# sheet3.net
KiCad netlist of a schematic drawn in Altium Designer
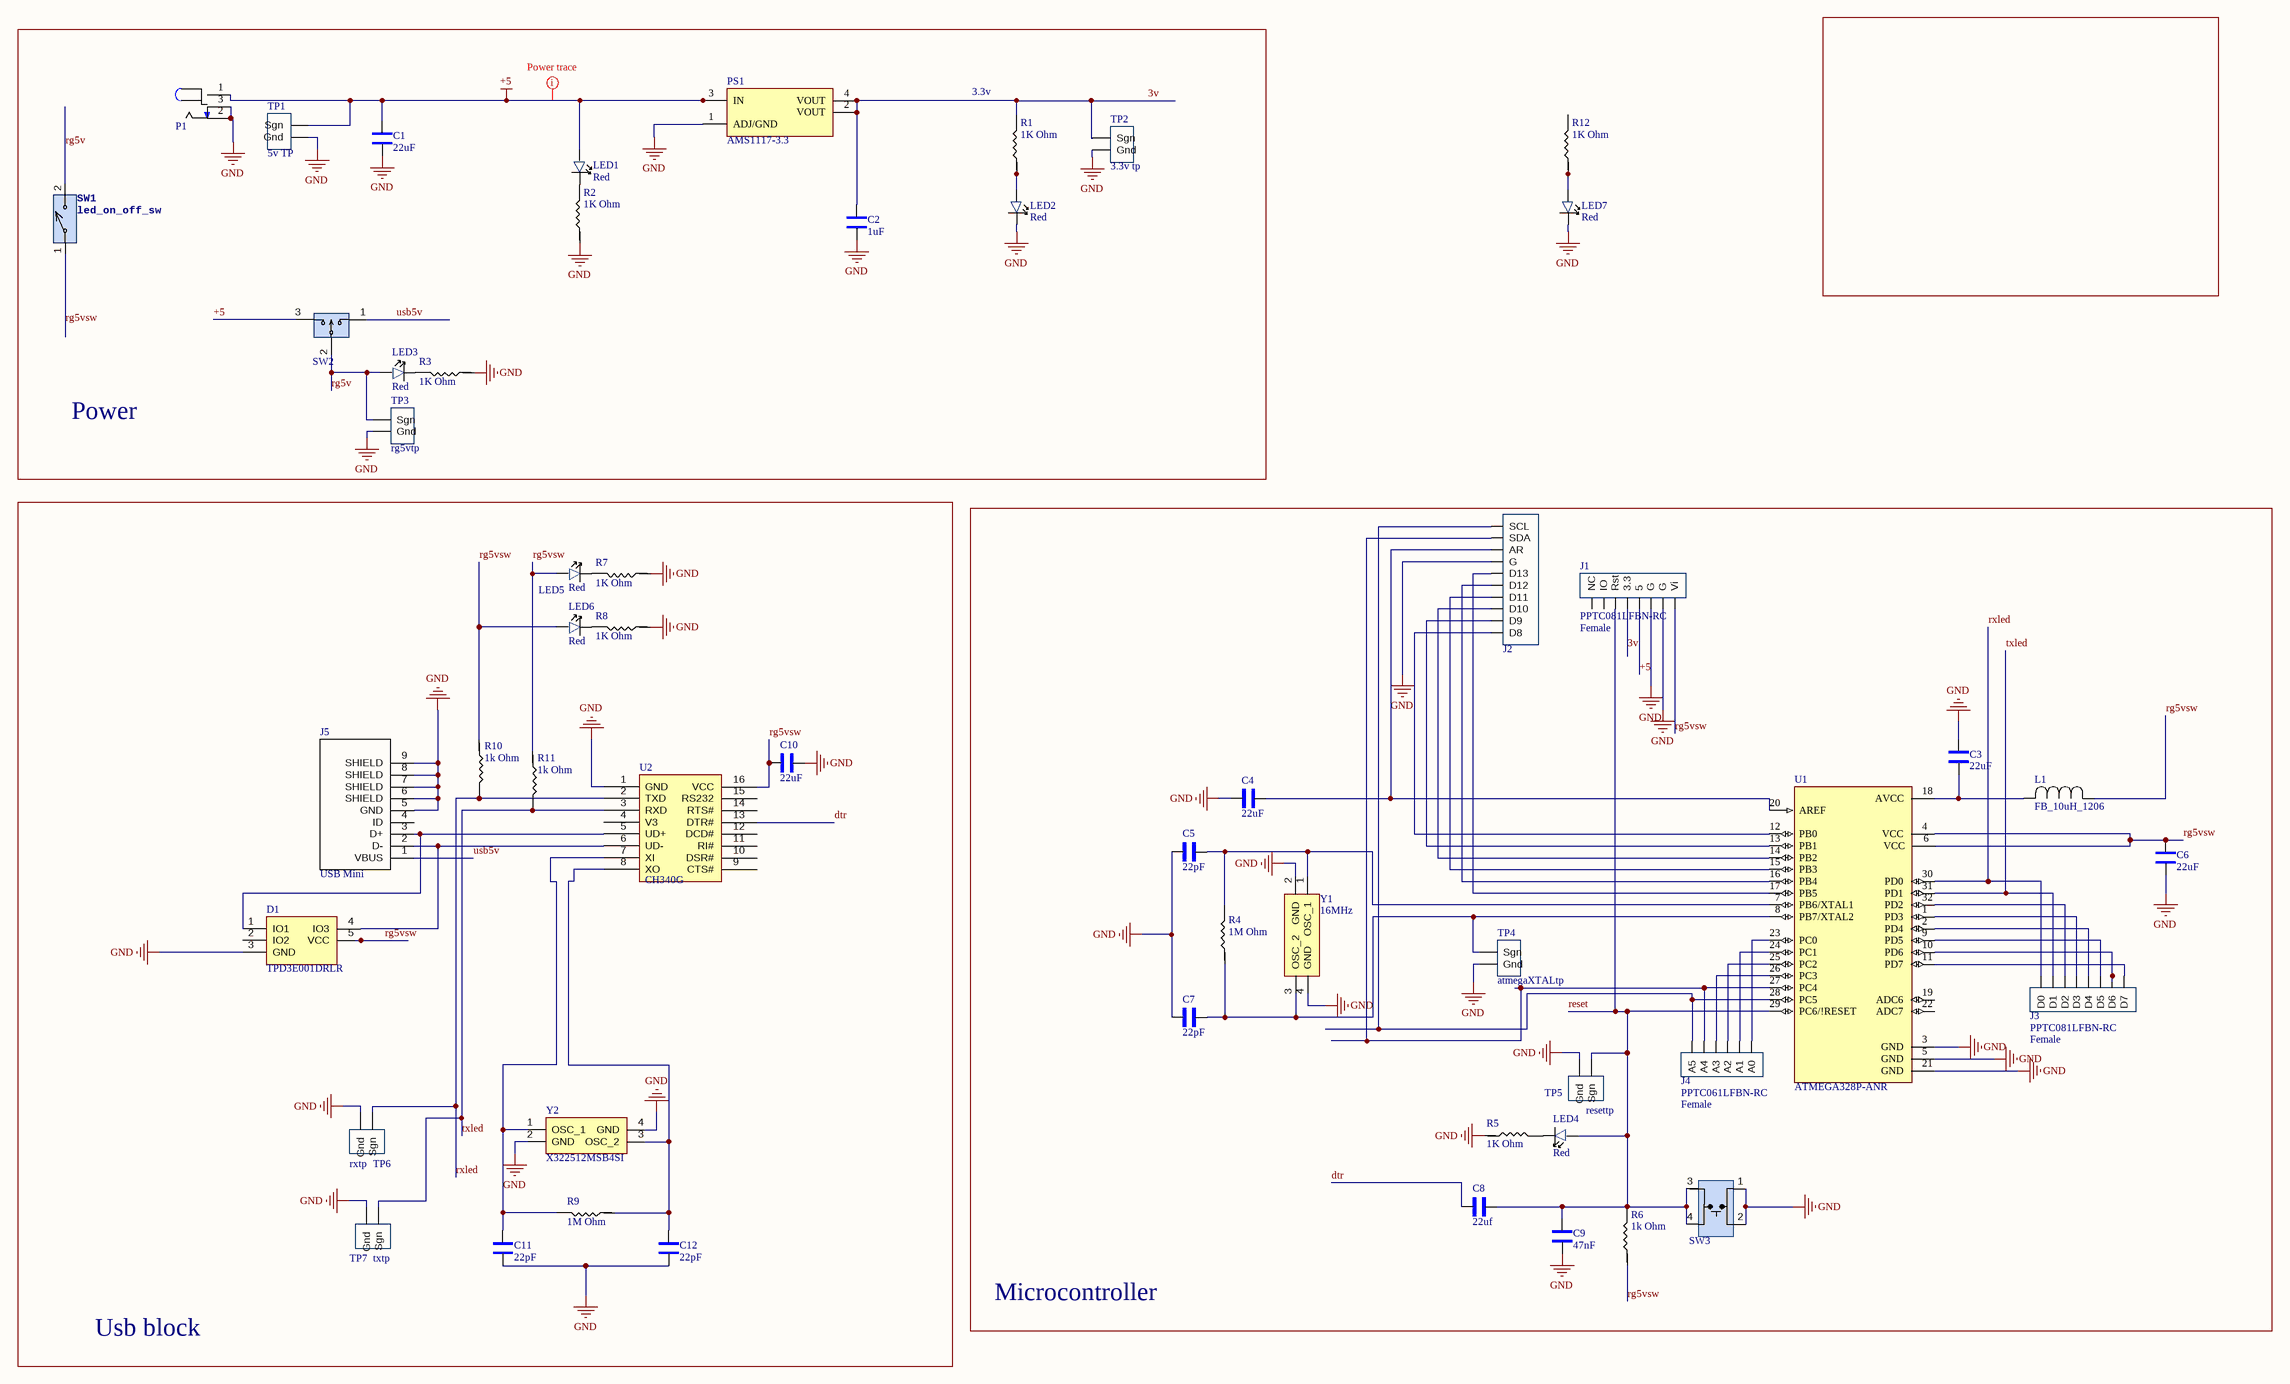
[diagram p0: sheet3.SchDoc]

(export (version "E")
  (design (tool "Eeschema 10.0.6"))
  (components
    (comp (ref "C1")
      (value "22uF")
      (footprint "1206_Passive_Capacitor")
      (description "22uF ±10% 25V X5R 1206 Multilayer Ceramic Capacitors MLCC - SMD/SMT RoHS")
      (fields (field (name "MFR PART #") "CL31A226KAHNNNE") (field (name "LCSC PART#") "C12891"))
      (libsource (lib "ECEN5730Lib_2023_05_DS") (part "C_22uF_1206"))
    )
    (comp (ref "C2")
      (value "1uF")
      (footprint "1206_Passive_Capacitor")
      (description "MULTILAYER CERAMIC CAPACITORS MLCC - SMD/SMT 1UF 50V 1206 ROHS")
      (fields (field (name "MFR PART #") "CL31B105KBHNNNE") (field (name "LCSC PART#") "C1848"))
      (libsource (lib "ECEN5730Lib_2023_05_DS") (part "C_1uF_1206"))
    )
    (comp (ref "C3")
      (value "22uF")
      (footprint "1206_Passive_Capacitor")
      (description "22uF ±10% 25V X5R 1206 Multilayer Ceramic Capacitors MLCC - SMD/SMT RoHS")
      (fields (field (name "MFR PART #") "CL31A226KAHNNNE") (field (name "LCSC PART#") "C12891"))
      (libsource (lib "ECEN5730Lib_2023_05_DS") (part "C_22uF_1206"))
    )
    (comp (ref "C4")
      (value "22uF")
      (footprint "1206_Passive_Capacitor")
      (description "22uF ±10% 25V X5R 1206 Multilayer Ceramic Capacitors MLCC - SMD/SMT RoHS")
      (fields (field (name "MFR PART #") "CL31A226KAHNNNE") (field (name "LCSC PART#") "C12891"))
      (libsource (lib "ECEN5730Lib_2023_05_DS") (part "C_22uF_1206"))
    )
    (comp (ref "C5")
      (value "22pF")
      (footprint "1206_Passive_Capacitor")
      (description "22pF ±5% 1kV C0G 1206 Multilayer Ceramic Capacitors MLCC - SMD/SMT RoHS")
      (fields (field (name "LCSC PART#") "C107174") (field (name "MFR PART #") "CC1206JKNPOCBN220"))
      (libsource (lib "ECEN5730Lib_2023_05_DS") (part "C_22pF_1206"))
    )
    (comp (ref "C6")
      (value "22uF")
      (footprint "1206_Passive_Capacitor")
      (description "22uF ±10% 25V X5R 1206 Multilayer Ceramic Capacitors MLCC - SMD/SMT RoHS")
      (fields (field (name "MFR PART #") "CL31A226KAHNNNE") (field (name "LCSC PART#") "C12891"))
      (libsource (lib "ECEN5730Lib_2023_05_DS") (part "C_22uF_1206"))
    )
    (comp (ref "C7")
      (value "22pF")
      (footprint "1206_Passive_Capacitor")
      (description "22pF ±5% 1kV C0G 1206 Multilayer Ceramic Capacitors MLCC - SMD/SMT RoHS")
      (fields (field (name "LCSC PART#") "C107174") (field (name "MFR PART #") "CC1206JKNPOCBN220"))
      (libsource (lib "ECEN5730Lib_2023_05_DS") (part "C_22pF_1206"))
    )
    (comp (ref "C8")
      (value "22uf")
      (footprint "1206_Passive_Capacitor")
      (description "MULTILAYER CERAMIC CAPACITORS MLCC - SMD/SMT 1UF 50V 1206 ROHS")
      (fields (field (name "MFR PART #") "CL31B105KBHNNNE") (field (name "LCSC PART#") "C1848"))
      (libsource (lib "ECEN5730Lib_2023_05_DS") (part "C_1uF_1206"))
    )
    (comp (ref "C9")
      (value "47nF")
      (footprint "1206_Passive_Capacitor")
      (description "47nF ±5% 50V C0G 1206 Multilayer Ceramic Capacitors MLCC - SMD/SMT RoHS")
      (fields (field (name "LCSC PART#") "C21812") (field (name "MFR PART #") "GRM31M5C1H473JA01L"))
      (libsource (lib "ECEN5730Lib_2023_05_DS") (part "C_47nF_1206"))
    )
    (comp (ref "C10")
      (value "22uF")
      (footprint "1206_Passive_Capacitor")
      (description "22uF ±10% 25V X5R 1206 Multilayer Ceramic Capacitors MLCC - SMD/SMT RoHS")
      (fields (field (name "MFR PART #") "CL31A226KAHNNNE") (field (name "LCSC PART#") "C12891"))
      (libsource (lib "ECEN5730Lib_2023_05_DS") (part "C_22uF_1206"))
    )
    (comp (ref "C11")
      (value "22pF")
      (footprint "1206_Passive_Capacitor")
      (description "22pF ±5% 1kV C0G 1206 Multilayer Ceramic Capacitors MLCC - SMD/SMT RoHS")
      (fields (field (name "LCSC PART#") "C107174") (field (name "MFR PART #") "CC1206JKNPOCBN220"))
      (libsource (lib "ECEN5730Lib_2023_05_DS") (part "C_22pF_1206"))
    )
    (comp (ref "C12")
      (value "22pF")
      (footprint "1206_Passive_Capacitor")
      (description "22pF ±5% 1kV C0G 1206 Multilayer Ceramic Capacitors MLCC - SMD/SMT RoHS")
      (fields (field (name "LCSC PART#") "C107174") (field (name "MFR PART #") "CC1206JKNPOCBN220"))
      (libsource (lib "ECEN5730Lib_2023_05_DS") (part "C_22pF_1206"))
    )
    (comp (ref "D1")
      (value "TPD3E001DRLR")
      (footprint "SOTFL50P160X60-5N")
      (description "Low-Capacitance 3-Channel +/-15KV ESD-Protection Array for High-Speed Data Interfaces")
      (fields (field (name "MOUSER PART NUMBER") "595-TPD3E001DRLR"))
      (libsource (lib "TPD3E001DRLR") (part "TPD3E001DRLR"))
    )
    (comp (ref "J1")
      (value "PPTC081LFBN-RC")
      (footprint "8_PIN_ARD-PWR_100MIL")
      (description "8 Position Header Connector 0.100\" (2.54mm) Through Hole Tin")
      (fields (field (name "LCSC PART#") "C27438") (field (name "ALTIUM_VALUE") "Female"))
      (libsource (lib "ECEN5730Lib_2023_05_DS") (part "JF_8_PIN_FEMA_ARD-Pwr"))
    )
    (comp (ref "J2")
      (value "PPTC101LFBN-RC")
      (footprint "10_PIN_ARDUINO_100MIL")
      (description "10 Position Header Connector 0.100\" (2.54mm) Through Hole Tin")
      (fields (field (name "LCSC PART#") "C225507"))
      (libsource (lib "ECEN5730Lib_2023_05_DS") (part "JF_10_PIN_FEMA_ARDUINO"))
    )
    (comp (ref "J3")
      (value "PPTC081LFBN-RC")
      (footprint "8_PIN_ARD-DIG_100MIL")
      (description "8 Position Header Connector 0.100\" (2.54mm) Through Hole Tin")
      (fields (field (name "LCSC PART#") "C27438") (field (name "ALTIUM_VALUE") "Female"))
      (libsource (lib "ECEN5730Lib_2023_05_DS") (part "JF_8_PIN_FEMA_ARD-Dig"))
    )
    (comp (ref "J4")
      (value "PPTC061LFBN-RC")
      (footprint "6_PIN_ARD-Analog_100mil")
      (description "6 Position Header Connector 0.100\" (2.54mm) Through Hole Tin")
      (fields (field (name "LCSC PART#") "C40877") (field (name "ALTIUM_VALUE") "Female"))
      (libsource (lib "ECEN5730Lib_2023_05_DS") (part "JF_6_PIN_FEMA_ARD-Anolog"))
    )
    (comp (ref "J5")
      (value "USB Mini")
      (footprint "USB_MINI_B")
      (description "Through Hole USB Connectors RoHS")
      (fields (field (name "LCSC PART#") "C46398") (field (name "MFR PART #") "920-462A2021D10102"))
      (libsource (lib "ECEN5730Lib_2023_05_DS") (part "J_USB_B_Mini"))
    )
    (comp (ref "L1")
      (value "FB_10uH_1206")
      (footprint "AIML-1206_ABR-M")
      (description "25mA 10uH ±10% 800mΩ 1206  Inductors (SMD) ROHS")
      (fields (field (name "MFR PART #") "CMI321609X100KT") (field (name "LCSC PART#") "C1051"))
      (libsource (lib "ECEN5730Lib_2023_05_DS") (part "FB_10uH_1206"))
    )
    (comp (ref "LED1")
      (value "Red")
      (footprint "LED_1206")
      (description "Red 621~631nm 1206 Light Emitting Diodes (LED) RoHS")
      (fields (field (name "MFR PART #") "15-21/R6C-FQ1R1B/2T") (field (name "LCSC PART#") "C93133"))
      (libsource (lib "ECEN5730Lib_2023_05_DS") (part "LED_RED_1206"))
    )
    (comp (ref "LED2")
      (value "Red")
      (footprint "LED_1206")
      (description "Red 621~631nm 1206 Light Emitting Diodes (LED) RoHS")
      (fields (field (name "MFR PART #") "15-21/R6C-FQ1R1B/2T") (field (name "LCSC PART#") "C93133"))
      (libsource (lib "ECEN5730Lib_2023_05_DS") (part "LED_RED_1206"))
    )
    (comp (ref "LED3")
      (value "Red")
      (footprint "LED_1206")
      (description "Red 621~631nm 1206 Light Emitting Diodes (LED) RoHS")
      (fields (field (name "MFR PART #") "15-21/R6C-FQ1R1B/2T") (field (name "LCSC PART#") "C93133"))
      (libsource (lib "ECEN5730Lib_2023_05_DS") (part "LED_RED_1206"))
    )
    (comp (ref "LED4")
      (value "Red")
      (footprint "LED_1206")
      (description "Red 621~631nm 1206 Light Emitting Diodes (LED) RoHS")
      (fields (field (name "MFR PART #") "15-21/R6C-FQ1R1B/2T") (field (name "LCSC PART#") "C93133"))
      (libsource (lib "ECEN5730Lib_2023_05_DS") (part "LED_RED_1206"))
    )
    (comp (ref "LED5")
      (value "Red")
      (footprint "LED_1206")
      (description "Red 621~631nm 1206 Light Emitting Diodes (LED) RoHS")
      (fields (field (name "MFR PART #") "15-21/R6C-FQ1R1B/2T") (field (name "LCSC PART#") "C93133"))
      (libsource (lib "ECEN5730Lib_2023_05_DS") (part "LED_RED_1206"))
    )
    (comp (ref "LED6")
      (value "Red")
      (footprint "LED_1206")
      (description "Red 621~631nm 1206 Light Emitting Diodes (LED) RoHS")
      (fields (field (name "MFR PART #") "15-21/R6C-FQ1R1B/2T") (field (name "LCSC PART#") "C93133"))
      (libsource (lib "ECEN5730Lib_2023_05_DS") (part "LED_RED_1206"))
    )
    (comp (ref "LED7")
      (value "Red")
      (footprint "LED_1206")
      (description "Red 621~631nm 1206 Light Emitting Diodes (LED) RoHS")
      (fields (field (name "MFR PART #") "15-21/R6C-FQ1R1B/2T") (field (name "LCSC PART#") "C93133"))
      (libsource (lib "ECEN5730Lib_2023_05_DS") (part "LED_RED_1206"))
    )
    (comp (ref "P1")
      (value "Power Jack")
      (footprint "Power_Jack")
      (description "Power Barrel Connector Jack 2.10mm ID (0.083\"), 5.50mm OD (0.217\") Through Hole, Right Angle")
      (fields (field (name "MFR PART #") "PJ-102A") (field (name "LCSC PART#") "C136744"))
      (libsource (lib "ECEN5730Lib_2023_05_DS") (part "P_Power Jack"))
    )
    (comp (ref "PS1")
      (value "AMS1117-3.3")
      (footprint "LDO")
      (description "LOW DROPOUT REGULATORS(LDO) POSITIVE FIXED 1.3V @ 800MA 15V 3.3V 1A SOT-223 ROHS")
      (fields (field (name "LCSC PART#") "C6186"))
      (libsource (lib "ECEN5730Lib_2023_05_DS") (part "PS_AMS_LDO_3v3"))
    )
    (comp (ref "R1")
      (value "1K Ohm")
      (footprint "1206_Passive_Resitor")
      (description "CHIP RESISTOR - SURFACE MOUNT 1KOHMS ±1% 1/4W 1206 ROHS")
      (fields (field (name "MFR PART #") "RNCP1206FTD1K00CT") (field (name "LCSC PART#") "C4410"))
      (libsource (lib "ECEN5730Lib_2023_05_DS") (part "R_1K_1206"))
    )
    (comp (ref "R2")
      (value "1K Ohm")
      (footprint "1206_Passive_Resitor")
      (description "CHIP RESISTOR - SURFACE MOUNT 1KOHMS ±1% 1/4W 1206 ROHS")
      (fields (field (name "MFR PART #") "RNCP1206FTD1K00CT") (field (name "LCSC PART#") "C4410"))
      (libsource (lib "ECEN5730Lib_2023_05_DS") (part "R_1K_1206"))
    )
    (comp (ref "R3")
      (value "1K Ohm")
      (footprint "1206_Passive_Resitor")
      (description "CHIP RESISTOR - SURFACE MOUNT 1KOHMS ±1% 1/4W 1206 ROHS")
      (fields (field (name "MFR PART #") "RNCP1206FTD1K00CT") (field (name "LCSC PART#") "C4410"))
      (libsource (lib "ECEN5730Lib_2023_05_DS") (part "R_1K_1206"))
    )
    (comp (ref "R4")
      (value "1M Ohm")
      (footprint "1206_Passive_Resitor")
      (description "CHIP RESISTOR - SURFACE MOUNT 1MOHMS ±1% 1/4W 1206 ROHS")
      (fields (field (name "MFR PART #") "RMCF1206JT1M00") (field (name "LCSC PART#") "C17927"))
      (libsource (lib "ECEN5730Lib_2023_05_DS") (part "R_1M_1206"))
    )
    (comp (ref "R5")
      (value "1K Ohm")
      (footprint "1206_Passive_Resitor")
      (description "CHIP RESISTOR - SURFACE MOUNT 1KOHMS ±1% 1/4W 1206 ROHS")
      (fields (field (name "MFR PART #") "RNCP1206FTD1K00CT") (field (name "LCSC PART#") "C4410"))
      (libsource (lib "ECEN5730Lib_2023_05_DS") (part "R_1K_1206"))
    )
    (comp (ref "R6")
      (value "1k Ohm")
      (footprint "1206_Passive_Resitor")
      (description "10 kOhms ±5% 0.25W, 1/4W Chip Resistor 1206 (3216 Metric) Automotive AEC-Q200 Thick Film")
      (fields (field (name "MFR PART #") "RMCF1206FT10K0") (field (name "LCSC PART#") "C17902"))
      (libsource (lib "ECEN5730Lib_2023_05_DS") (part "R_10KOhm_1206"))
    )
    (comp (ref "R7")
      (value "1K Ohm")
      (footprint "1206_Passive_Resitor")
      (description "CHIP RESISTOR - SURFACE MOUNT 1KOHMS ±1% 1/4W 1206 ROHS")
      (fields (field (name "MFR PART #") "RNCP1206FTD1K00CT") (field (name "LCSC PART#") "C4410"))
      (libsource (lib "ECEN5730Lib_2023_05_DS") (part "R_1K_1206"))
    )
    (comp (ref "R8")
      (value "1K Ohm")
      (footprint "1206_Passive_Resitor")
      (description "CHIP RESISTOR - SURFACE MOUNT 1KOHMS ±1% 1/4W 1206 ROHS")
      (fields (field (name "MFR PART #") "RNCP1206FTD1K00CT") (field (name "LCSC PART#") "C4410"))
      (libsource (lib "ECEN5730Lib_2023_05_DS") (part "R_1K_1206"))
    )
    (comp (ref "R9")
      (value "1M Ohm")
      (footprint "1206_Passive_Resitor")
      (description "CHIP RESISTOR - SURFACE MOUNT 1MOHMS ±1% 1/4W 1206 ROHS")
      (fields (field (name "MFR PART #") "RMCF1206JT1M00") (field (name "LCSC PART#") "C17927"))
      (libsource (lib "ECEN5730Lib_2023_05_DS") (part "R_1M_1206"))
    )
    (comp (ref "R10")
      (value "1k Ohm")
      (footprint "1206_Passive_Resitor")
      (description "CHIP RESISTOR - SURFACE MOUNT 1MOHMS ±1% 1/4W 1206 ROHS")
      (fields (field (name "MFR PART #") "RMCF1206JT1M00") (field (name "LCSC PART#") "C17927"))
      (libsource (lib "ECEN5730Lib_2023_05_DS") (part "R_1M_1206"))
    )
    (comp (ref "R11")
      (value "1k Ohm")
      (footprint "1206_Passive_Resitor")
      (description "CHIP RESISTOR - SURFACE MOUNT 1MOHMS ±1% 1/4W 1206 ROHS")
      (fields (field (name "MFR PART #") "RMCF1206JT1M00") (field (name "LCSC PART#") "C17927"))
      (libsource (lib "ECEN5730Lib_2023_05_DS") (part "R_1M_1206"))
    )
    (comp (ref "R12")
      (value "1K Ohm")
      (footprint "1206_Passive_Resitor")
      (description "CHIP RESISTOR - SURFACE MOUNT 1KOHMS ±1% 1/4W 1206 ROHS")
      (fields (field (name "MFR PART #") "RNCP1206FTD1K00CT") (field (name "LCSC PART#") "C4410"))
      (libsource (lib "ECEN5730Lib_2023_05_DS") (part "R_1K_1206"))
    )
    (comp (ref "SW1")
      (value "led_on_off_sw")
      (footprint "2Pin-Header-Conn")
      (description "2Pin Header")
      (fields (field (name "LCSC PART#") "C124375"))
      (libsource (lib "ECEN5730Lib_2023_05_DS") (part "SW_2Pin_100mil_Switch"))
    )
    (comp (ref "SW2")
      (value "PREC003SAAN-RC")
      (footprint "3_PIN_100mil")
      (description "Connector Header Through Hole 3 position 0.100\" (2.54mm)")
      (fields (field (name "LCSC PART#") "C49257"))
      (libsource (lib "ECEN5730Lib_2023_05_DS") (part "SW_3Pin_100mil_Switch"))
    )
    (comp (ref "SW3")
      (value "TL3305AF160QG")
      (footprint "Switch_JLC")
      (description "Tactile Switch SPST-NO Top Actuated Surface Mount")
      (fields (field (name "MFR PART #") "KH-4.5X4.5X4.3H-STM") (field (name "LCSC PART#") "C2837550"))
      (libsource (lib "ECEN5730Lib_2023_05_DS") (part "SW_Push_Button_JLC"))
    )
    (comp (ref "TP1")
      (value "5v TP")
      (footprint "TP10x_Probe")
      (description "Test Point 300 mil centers")
      (libsource (lib "ECEN5730Lib_2023_05_DS") (part "TP_10x_Probe"))
    )
    (comp (ref "TP2")
      (value "3.3v tp")
      (footprint "TP10x_Probe")
      (description "Test Point 300 mil centers")
      (libsource (lib "") (part "TP_10x_Probe_1"))
    )
    (comp (ref "TP3")
      (value "rg5vtp")
      (footprint "TP10x_Probe")
      (description "Test Point 300 mil centers")
      (libsource (lib "") (part "TP_10x_Probe_1"))
    )
    (comp (ref "TP4")
      (value "atmegaXTALtp")
      (footprint "TP10x_Probe")
      (description "Test Point 300 mil centers")
      (libsource (lib "") (part "TP_10x_Probe_1"))
    )
    (comp (ref "TP5")
      (value "resettp")
      (footprint "TP10x_Probe")
      (description "Test Point 300 mil centers")
      (libsource (lib "ECEN5730Lib_2023_05_DS") (part "TP_10x_Probe"))
    )
    (comp (ref "TP6")
      (value "rxtp")
      (footprint "TP10x_Probe")
      (description "Test Point 300 mil centers")
      (libsource (lib "ECEN5730Lib_2023_05_DS") (part "TP_10x_Probe"))
    )
    (comp (ref "TP7")
      (value "txtp")
      (footprint "TP10x_Probe")
      (description "Test Point 300 mil centers")
      (libsource (lib "ECEN5730Lib_2023_05_DS") (part "TP_10x_Probe"))
    )
    (comp (ref "U1")
      (value "ATMEGA328P-ANR")
      (footprint "ATMega328P")
      (description "AVR AVR® ATmega Microcontroller IC 8-Bit 20MHz 32KB (16K x 16) FLASH 32-TQFP (7x7)")
      (fields (field (name "MFR PART #") "ATMEGA328P-AU") (field (name "LCSC PART#") "C14877"))
      (libsource (lib "ECEN5730Lib_2023_05_DS") (part "U_ATMega328P"))
    )
    (comp (ref "U2")
      (value "CH340G")
      (footprint "USB to serial")
      (description "Transceiver USB 2.0 2Mbps SOP-16_150mil USB ICs RoHS")
      (fields (field (name "LCSC PART#") "C14267"))
      (libsource (lib "ECEN5730Lib_2023_05_DS") (part "U_USBtoSerial"))
    )
    (comp (ref "Y1")
      (value "16MHz")
      (footprint "Crystal resonator")
      (description "±10ppm 16000000Hz -40℃~85℃ 贴片无源晶振 60Ω 9pF SMD3225-4P Crystals ROHS")
      (fields (field (name "LCSC PART#") "C13738") (field (name "MFR PART #") "X322516MLB4SI"))
      (libsource (lib "ECEN5730Lib_2023_05_DS") (part "X_16Mhz_Res"))
    )
    (comp (ref "Y2")
      (value "X322512MSB4SI")
      (footprint "Crystal resonator")
      (description "SMD Crystal Resonators 12MHz ±10ppm SMD-3225_4P RoHS")
      (fields (field (name "LCSC PART#") "C9002"))
      (libsource (lib "ECEN5730Lib_2023_05_DS") (part "X_12MHz_Res"))
    )
  )
  (nets
    (net (code "1") (name "+5") (class "Default")
      (node (ref "C1") (pin "2") (pinfunction "2_2") (pintype "passive"))
      (node (ref "J1") (pin "5") (pinfunction "5_5") (pintype "passive"))
      (node (ref "LED1") (pin "1") (pinfunction "1_1") (pintype "passive"))
      (node (ref "P1") (pin "1") (pinfunction "1_1") (pintype "power_in"))
      (node (ref "PS1") (pin "3") (pinfunction "IN_3") (pintype "power_in"))
      (node (ref "SW2") (pin "3") (pinfunction "3_3") (pintype "passive"))
      (node (ref "TP1") (pin "1") (pinfunction "Sgn_1") (pintype "passive"))
    )
    (net (code "2") (name "/3v") (class "Default")
      (node (ref "C2") (pin "2") (pinfunction "2_2") (pintype "passive"))
      (node (ref "J1") (pin "4") (pinfunction "3.3_4") (pintype "passive"))
      (node (ref "PS1") (pin "2") (pinfunction "VOUT_2") (pintype "power_in"))
      (node (ref "PS1") (pin "4") (pinfunction "VOUT_4") (pintype "power_in"))
      (node (ref "R1") (pin "2") (pinfunction "2_2") (pintype "passive"))
      (node (ref "TP2") (pin "1") (pinfunction "Sgn_1") (pintype "passive"))
    )
    (net (code "3") (name "/dtr") (class "Default")
      (node (ref "C8") (pin "1") (pinfunction "1_1") (pintype "passive"))
      (node (ref "U2") (pin "13") (pinfunction "DTR#_13") (pintype "passive"))
    )
    (net (code "4") (name "/reset") (class "Default")
      (node (ref "C8") (pin "2") (pinfunction "2_2") (pintype "passive"))
      (node (ref "C9") (pin "2") (pinfunction "2_2") (pintype "passive"))
      (node (ref "J1") (pin "3") (pinfunction "Rst_3") (pintype "passive"))
      (node (ref "LED4") (pin "1") (pinfunction "1_1") (pintype "passive"))
      (node (ref "R6") (pin "2") (pinfunction "2_2") (pintype "passive"))
      (node (ref "SW3") (pin "3") (pinfunction "3_3") (pintype "passive"))
      (node (ref "SW3") (pin "4") (pinfunction "4_4") (pintype "passive"))
      (node (ref "TP5") (pin "1") (pinfunction "Sgn_1") (pintype "passive"))
      (node (ref "U1") (pin "29") (pinfunction "PC6/!RESET_29") (pintype "bidirectional"))
    )
    (net (code "5") (name "/rg5v") (class "Default")
      (node (ref "LED3") (pin "1") (pinfunction "1_1") (pintype "passive"))
      (node (ref "SW1") (pin "2") (pinfunction "2_2") (pintype "passive"))
      (node (ref "SW2") (pin "2") (pinfunction "2_2") (pintype "passive"))
      (node (ref "TP3") (pin "1") (pinfunction "Sgn_1") (pintype "passive"))
    )
    (net (code "6") (name "/rg5vsw") (class "Default")
      (node (ref "C10") (pin "1") (pinfunction "1_1") (pintype "passive"))
      (node (ref "C6") (pin "2") (pinfunction "2_2") (pintype "passive"))
      (node (ref "D1") (pin "5") (pinfunction "VCC_5") (pintype "passive"))
      (node (ref "J1") (pin "8") (pinfunction "Vi_8") (pintype "passive"))
      (node (ref "L1") (pin "1") (pinfunction "1_1") (pintype "passive"))
      (node (ref "LED5") (pin "1") (pinfunction "1_1") (pintype "passive"))
      (node (ref "LED6") (pin "1") (pinfunction "1_1") (pintype "passive"))
      (node (ref "R10") (pin "1") (pinfunction "1_1") (pintype "passive"))
      (node (ref "R11") (pin "1") (pinfunction "1_1") (pintype "passive"))
      (node (ref "R6") (pin "1") (pinfunction "1_1") (pintype "passive"))
      (node (ref "SW1") (pin "1") (pinfunction "1_1") (pintype "passive"))
      (node (ref "U1") (pin "4") (pinfunction "VCC_4") (pintype "power_in"))
      (node (ref "U1") (pin "6") (pinfunction "VCC_6") (pintype "power_in"))
      (node (ref "U2") (pin "16") (pinfunction "VCC_16") (pintype "passive"))
    )
    (net (code "7") (name "/rxled") (class "Default")
      (node (ref "J3") (pin "8") (pinfunction "D0_8") (pintype "passive"))
      (node (ref "R10") (pin "2") (pinfunction "2_2") (pintype "passive"))
      (node (ref "TP6") (pin "1") (pinfunction "Sgn_1") (pintype "passive"))
      (node (ref "U1") (pin "30") (pinfunction "PD0_30") (pintype "bidirectional"))
      (node (ref "U2") (pin "2") (pinfunction "TXD_2") (pintype "passive"))
    )
    (net (code "8") (name "/txled") (class "Default")
      (node (ref "J3") (pin "7") (pinfunction "D1_7") (pintype "passive"))
      (node (ref "R11") (pin "2") (pinfunction "2_2") (pintype "passive"))
      (node (ref "TP7") (pin "1") (pinfunction "Sgn_1") (pintype "passive"))
      (node (ref "U1") (pin "31") (pinfunction "PD1_31") (pintype "bidirectional"))
      (node (ref "U2") (pin "3") (pinfunction "RXD_3") (pintype "passive"))
    )
    (net (code "9") (name "/usb5v") (class "Default")
      (node (ref "J5") (pin "1") (pinfunction "VBUS_1") (pintype "passive"))
      (node (ref "SW2") (pin "1") (pinfunction "1_1") (pintype "passive"))
    )
    (net (code "10") (name "GND") (class "Default")
      (node (ref "C1") (pin "1") (pinfunction "1_1") (pintype "passive"))
      (node (ref "C10") (pin "2") (pinfunction "2_2") (pintype "passive"))
      (node (ref "C11") (pin "1") (pinfunction "1_1") (pintype "passive"))
      (node (ref "C12") (pin "1") (pinfunction "1_1") (pintype "passive"))
      (node (ref "C2") (pin "1") (pinfunction "1_1") (pintype "passive"))
      (node (ref "C3") (pin "2") (pinfunction "2_2") (pintype "passive"))
      (node (ref "C4") (pin "2") (pinfunction "2_2") (pintype "passive"))
      (node (ref "C5") (pin "1") (pinfunction "1_1") (pintype "passive"))
      (node (ref "C6") (pin "1") (pinfunction "1_1") (pintype "passive"))
      (node (ref "C7") (pin "1") (pinfunction "1_1") (pintype "passive"))
      (node (ref "C9") (pin "1") (pinfunction "1_1") (pintype "passive"))
      (node (ref "D1") (pin "3") (pinfunction "GND_3") (pintype "passive"))
      (node (ref "J1") (pin "6") (pinfunction "G_6") (pintype "passive"))
      (node (ref "J1") (pin "7") (pinfunction "G_7") (pintype "passive"))
      (node (ref "J2") (pin "4") (pinfunction "G_4") (pintype "passive"))
      (node (ref "J5") (pin "5") (pinfunction "GND_5") (pintype "passive"))
      (node (ref "J5") (pin "6") (pinfunction "SHIELD_6") (pintype "passive"))
      (node (ref "J5") (pin "7") (pinfunction "SHIELD_7") (pintype "passive"))
      (node (ref "J5") (pin "8") (pinfunction "SHIELD_8") (pintype "passive"))
      (node (ref "J5") (pin "9") (pinfunction "SHIELD_9") (pintype "passive"))
      (node (ref "LED2") (pin "2") (pinfunction "2_2") (pintype "passive"))
      (node (ref "LED7") (pin "2") (pinfunction "2_2") (pintype "passive"))
      (node (ref "P1") (pin "2") (pinfunction "2_2") (pintype "power_in"))
      (node (ref "P1") (pin "3") (pinfunction "3_3") (pintype "power_in"))
      (node (ref "PS1") (pin "1") (pinfunction "ADJ/GND_1") (pintype "passive"))
      (node (ref "R2") (pin "1") (pinfunction "1_1") (pintype "passive"))
      (node (ref "R3") (pin "1") (pinfunction "1_1") (pintype "passive"))
      (node (ref "R5") (pin "1") (pinfunction "1_1") (pintype "passive"))
      (node (ref "R7") (pin "1") (pinfunction "1_1") (pintype "passive"))
      (node (ref "R8") (pin "1") (pinfunction "1_1") (pintype "passive"))
      (node (ref "SW3") (pin "1") (pinfunction "1_1") (pintype "passive"))
      (node (ref "SW3") (pin "2") (pinfunction "2_2") (pintype "passive"))
      (node (ref "TP1") (pin "2") (pinfunction "Gnd_2") (pintype "passive"))
      (node (ref "TP2") (pin "2") (pinfunction "Gnd_2") (pintype "passive"))
      (node (ref "TP3") (pin "2") (pinfunction "Gnd_2") (pintype "passive"))
      (node (ref "TP4") (pin "2") (pinfunction "Gnd_2") (pintype "passive"))
      (node (ref "TP5") (pin "2") (pinfunction "Gnd_2") (pintype "passive"))
      (node (ref "TP6") (pin "2") (pinfunction "Gnd_2") (pintype "passive"))
      (node (ref "TP7") (pin "2") (pinfunction "Gnd_2") (pintype "passive"))
      (node (ref "U1") (pin "21") (pinfunction "GND_21") (pintype "power_in"))
      (node (ref "U1") (pin "3") (pinfunction "GND_3") (pintype "power_in"))
      (node (ref "U1") (pin "5") (pinfunction "GND_5") (pintype "power_in"))
      (node (ref "U2") (pin "1") (pinfunction "GND_1") (pintype "passive"))
      (node (ref "Y1") (pin "2") (pinfunction "GND_2") (pintype "passive"))
      (node (ref "Y1") (pin "4") (pinfunction "GND_4") (pintype "passive"))
      (node (ref "Y2") (pin "2") (pinfunction "GND_2") (pintype "passive"))
      (node (ref "Y2") (pin "4") (pinfunction "GND_4") (pintype "passive"))
    )
    (net (code "11") (name "Net-(D1-IO1)") (class "Default")
      (node (ref "D1") (pin "1") (pinfunction "IO1_1") (pintype "passive"))
      (node (ref "J5") (pin "3") (pinfunction "D+_3") (pintype "passive"))
      (node (ref "U2") (pin "5") (pinfunction "UD+_5") (pintype "passive"))
    )
    (net (code "12") (name "Net-(D1-IO3)") (class "Default")
      (node (ref "D1") (pin "4") (pinfunction "IO3_4") (pintype "passive"))
      (node (ref "J5") (pin "2") (pinfunction "D-_2") (pintype "passive"))
      (node (ref "U2") (pin "6") (pinfunction "UD-_6") (pintype "passive"))
    )
    (net (code "13") (name "Net-(J2-AR)") (class "Default")
      (node (ref "C4") (pin "1") (pinfunction "1_1") (pintype "passive"))
      (node (ref "J2") (pin "3") (pinfunction "AR_3") (pintype "passive"))
      (node (ref "U1") (pin "20") (pinfunction "AREF_20") (pintype "input"))
    )
    (net (code "14") (name "Net-(J2-D8)") (class "Default")
      (node (ref "J2") (pin "10") (pinfunction "D8_10") (pintype "passive"))
      (node (ref "U1") (pin "12") (pinfunction "PB0_12") (pintype "bidirectional"))
    )
    (net (code "15") (name "Net-(J2-D9)") (class "Default")
      (node (ref "J2") (pin "9") (pinfunction "D9_9") (pintype "passive"))
      (node (ref "U1") (pin "13") (pinfunction "PB1_13") (pintype "bidirectional"))
    )
    (net (code "16") (name "Net-(J2-D10)") (class "Default")
      (node (ref "J2") (pin "8") (pinfunction "D10_8") (pintype "passive"))
      (node (ref "U1") (pin "14") (pinfunction "PB2_14") (pintype "bidirectional"))
    )
    (net (code "17") (name "Net-(J2-D11)") (class "Default")
      (node (ref "J2") (pin "7") (pinfunction "D11_7") (pintype "passive"))
      (node (ref "U1") (pin "15") (pinfunction "PB3_15") (pintype "bidirectional"))
    )
    (net (code "18") (name "Net-(J2-D12)") (class "Default")
      (node (ref "J2") (pin "6") (pinfunction "D12_6") (pintype "passive"))
      (node (ref "U1") (pin "16") (pinfunction "PB4_16") (pintype "bidirectional"))
    )
    (net (code "19") (name "Net-(J2-D13)") (class "Default")
      (node (ref "J2") (pin "5") (pinfunction "D13_5") (pintype "passive"))
      (node (ref "U1") (pin "17") (pinfunction "PB5_17") (pintype "bidirectional"))
    )
    (net (code "20") (name "Net-(J2-SCL)") (class "Default")
      (node (ref "J2") (pin "1") (pinfunction "SCL_1") (pintype "passive"))
      (node (ref "J4") (pin "6") (pinfunction "A5_6") (pintype "passive"))
      (node (ref "U1") (pin "28") (pinfunction "PC5_28") (pintype "bidirectional"))
    )
    (net (code "21") (name "Net-(J2-SDA)") (class "Default")
      (node (ref "J2") (pin "2") (pinfunction "SDA_2") (pintype "passive"))
      (node (ref "J4") (pin "5") (pinfunction "A4_5") (pintype "passive"))
      (node (ref "U1") (pin "27") (pinfunction "PC4_27") (pintype "bidirectional"))
    )
    (net (code "22") (name "Net-(J3-D2)") (class "Default")
      (node (ref "J3") (pin "6") (pinfunction "D2_6") (pintype "passive"))
      (node (ref "U1") (pin "32") (pinfunction "PD2_32") (pintype "bidirectional"))
    )
    (net (code "23") (name "Net-(J3-D3)") (class "Default")
      (node (ref "J3") (pin "5") (pinfunction "D3_5") (pintype "passive"))
      (node (ref "U1") (pin "1") (pinfunction "PD3_1") (pintype "bidirectional"))
    )
    (net (code "24") (name "Net-(J3-D4)") (class "Default")
      (node (ref "J3") (pin "4") (pinfunction "D4_4") (pintype "passive"))
      (node (ref "U1") (pin "2") (pinfunction "PD4_2") (pintype "bidirectional"))
    )
    (net (code "25") (name "Net-(J3-D5)") (class "Default")
      (node (ref "J3") (pin "3") (pinfunction "D5_3") (pintype "passive"))
      (node (ref "U1") (pin "9") (pinfunction "PD5_9") (pintype "bidirectional"))
    )
    (net (code "26") (name "Net-(J3-D6)") (class "Default")
      (node (ref "J3") (pin "2") (pinfunction "D6_2") (pintype "passive"))
      (node (ref "U1") (pin "10") (pinfunction "PD6_10") (pintype "bidirectional"))
    )
    (net (code "27") (name "Net-(J3-D7)") (class "Default")
      (node (ref "J3") (pin "1") (pinfunction "D7_1") (pintype "passive"))
      (node (ref "U1") (pin "11") (pinfunction "PD7_11") (pintype "bidirectional"))
    )
    (net (code "28") (name "Net-(J4-A0)") (class "Default")
      (node (ref "J4") (pin "1") (pinfunction "A0_1") (pintype "passive"))
      (node (ref "U1") (pin "23") (pinfunction "PC0_23") (pintype "bidirectional"))
    )
    (net (code "29") (name "Net-(J4-A1)") (class "Default")
      (node (ref "J4") (pin "2") (pinfunction "A1_2") (pintype "passive"))
      (node (ref "U1") (pin "24") (pinfunction "PC1_24") (pintype "bidirectional"))
    )
    (net (code "30") (name "Net-(J4-A2)") (class "Default")
      (node (ref "J4") (pin "3") (pinfunction "A2_3") (pintype "passive"))
      (node (ref "U1") (pin "25") (pinfunction "PC2_25") (pintype "bidirectional"))
    )
    (net (code "31") (name "Net-(J4-A3)") (class "Default")
      (node (ref "J4") (pin "4") (pinfunction "A3_4") (pintype "passive"))
      (node (ref "U1") (pin "26") (pinfunction "PC3_26") (pintype "bidirectional"))
    )
    (net (code "32") (name "Net-(LED1-Pad2)") (class "Default")
      (node (ref "LED1") (pin "2") (pinfunction "2_2") (pintype "passive"))
      (node (ref "R2") (pin "2") (pinfunction "2_2") (pintype "passive"))
    )
    (net (code "33") (name "Net-(LED2-Pad1)") (class "Default")
      (node (ref "LED2") (pin "1") (pinfunction "1_1") (pintype "passive"))
      (node (ref "R1") (pin "1") (pinfunction "1_1") (pintype "passive"))
    )
    (net (code "34") (name "Net-(LED3-Pad2)") (class "Default")
      (node (ref "LED3") (pin "2") (pinfunction "2_2") (pintype "passive"))
      (node (ref "R3") (pin "2") (pinfunction "2_2") (pintype "passive"))
    )
    (net (code "35") (name "Net-(LED4-Pad2)") (class "Default")
      (node (ref "LED4") (pin "2") (pinfunction "2_2") (pintype "passive"))
      (node (ref "R5") (pin "2") (pinfunction "2_2") (pintype "passive"))
    )
    (net (code "36") (name "Net-(LED5-Pad2)") (class "Default")
      (node (ref "LED5") (pin "2") (pinfunction "2_2") (pintype "passive"))
      (node (ref "R7") (pin "2") (pinfunction "2_2") (pintype "passive"))
    )
    (net (code "37") (name "Net-(LED6-Pad2)") (class "Default")
      (node (ref "LED6") (pin "2") (pinfunction "2_2") (pintype "passive"))
      (node (ref "R8") (pin "2") (pinfunction "2_2") (pintype "passive"))
    )
    (net (code "38") (name "Net-(LED7-Pad1)") (class "Default")
      (node (ref "LED7") (pin "1") (pinfunction "1_1") (pintype "passive"))
      (node (ref "R12") (pin "1") (pinfunction "1_1") (pintype "passive"))
    )
    (net (code "39") (name "Net-(TP4-Sgn)") (class "Default")
      (node (ref "C7") (pin "2") (pinfunction "2_2") (pintype "passive"))
      (node (ref "R4") (pin "1") (pinfunction "1_1") (pintype "passive"))
      (node (ref "TP4") (pin "1") (pinfunction "Sgn_1") (pintype "passive"))
      (node (ref "U1") (pin "8") (pinfunction "PB7/XTAL2_8") (pintype "bidirectional"))
      (node (ref "Y1") (pin "3") (pinfunction "OSC_2_3") (pintype "passive"))
    )
    (net (code "40") (name "Net-(U1-AVCC)") (class "Default")
      (node (ref "C3") (pin "1") (pinfunction "1_1") (pintype "passive"))
      (node (ref "L1") (pin "2") (pinfunction "2_2") (pintype "passive"))
      (node (ref "U1") (pin "18") (pinfunction "AVCC_18") (pintype "power_in"))
    )
    (net (code "41") (name "Net-(U1-PB6{slash}XTAL1)") (class "Default")
      (node (ref "C5") (pin "2") (pinfunction "2_2") (pintype "passive"))
      (node (ref "R4") (pin "2") (pinfunction "2_2") (pintype "passive"))
      (node (ref "U1") (pin "7") (pinfunction "PB6/XTAL1_7") (pintype "bidirectional"))
      (node (ref "Y1") (pin "1") (pinfunction "OSC_1_1") (pintype "passive"))
    )
    (net (code "42") (name "Net-(U2-XI)") (class "Default")
      (node (ref "C11") (pin "2") (pinfunction "2_2") (pintype "passive"))
      (node (ref "R9") (pin "2") (pinfunction "2_2") (pintype "passive"))
      (node (ref "U2") (pin "7") (pinfunction "XI_7") (pintype "passive"))
      (node (ref "Y2") (pin "1") (pinfunction "OSC_1_1") (pintype "passive"))
    )
    (net (code "43") (name "Net-(U2-XO)") (class "Default")
      (node (ref "C12") (pin "2") (pinfunction "2_2") (pintype "passive"))
      (node (ref "R9") (pin "1") (pinfunction "1_1") (pintype "passive"))
      (node (ref "U2") (pin "8") (pinfunction "XO_8") (pintype "passive"))
      (node (ref "Y2") (pin "3") (pinfunction "OSC_2_3") (pintype "passive"))
    )
    (net (code "44") (name "unconnected-(D1-IO2-Pad2)") (class "Default")
      (node (ref "D1") (pin "2") (pinfunction "IO2_2") (pintype "passive"))
    )
    (net (code "45") (name "unconnected-(J1-IO-Pad2)") (class "Default")
      (node (ref "J1") (pin "2") (pinfunction "IO_2") (pintype "passive"))
    )
    (net (code "46") (name "unconnected-(J1-NC-Pad1)") (class "Default")
      (node (ref "J1") (pin "1") (pinfunction "NC_1") (pintype "passive"))
    )
    (net (code "47") (name "unconnected-(J5-ID-Pad4)") (class "Default")
      (node (ref "J5") (pin "4") (pinfunction "ID_4") (pintype "passive"))
    )
    (net (code "48") (name "unconnected-(R12-Pad2)") (class "Default")
      (node (ref "R12") (pin "2") (pinfunction "2_2") (pintype "passive"))
    )
    (net (code "49") (name "unconnected-(U1-ADC6-Pad19)") (class "Default")
      (node (ref "U1") (pin "19") (pinfunction "ADC6_19") (pintype "bidirectional"))
    )
    (net (code "50") (name "unconnected-(U1-ADC7-Pad22)") (class "Default")
      (node (ref "U1") (pin "22") (pinfunction "ADC7_22") (pintype "bidirectional"))
    )
    (net (code "51") (name "unconnected-(U2-CTS#-Pad9)") (class "Default")
      (node (ref "U2") (pin "9") (pinfunction "CTS#_9") (pintype "passive"))
    )
    (net (code "52") (name "unconnected-(U2-DCD#-Pad12)") (class "Default")
      (node (ref "U2") (pin "12") (pinfunction "DCD#_12") (pintype "passive"))
    )
    (net (code "53") (name "unconnected-(U2-DSR#-Pad10)") (class "Default")
      (node (ref "U2") (pin "10") (pinfunction "DSR#_10") (pintype "passive"))
    )
    (net (code "54") (name "unconnected-(U2-RI#-Pad11)") (class "Default")
      (node (ref "U2") (pin "11") (pinfunction "RI#_11") (pintype "passive"))
    )
    (net (code "55") (name "unconnected-(U2-RS232-Pad15)") (class "Default")
      (node (ref "U2") (pin "15") (pinfunction "RS232_15") (pintype "passive"))
    )
    (net (code "56") (name "unconnected-(U2-RTS#-Pad14)") (class "Default")
      (node (ref "U2") (pin "14") (pinfunction "RTS#_14") (pintype "passive"))
    )
    (net (code "57") (name "unconnected-(U2-V3-Pad4)") (class "Default")
      (node (ref "U2") (pin "4") (pinfunction "V3_4") (pintype "passive"))
    )
  )
)
